# controller.net
KiCad netlist of a schematic drawn in Altium Designer
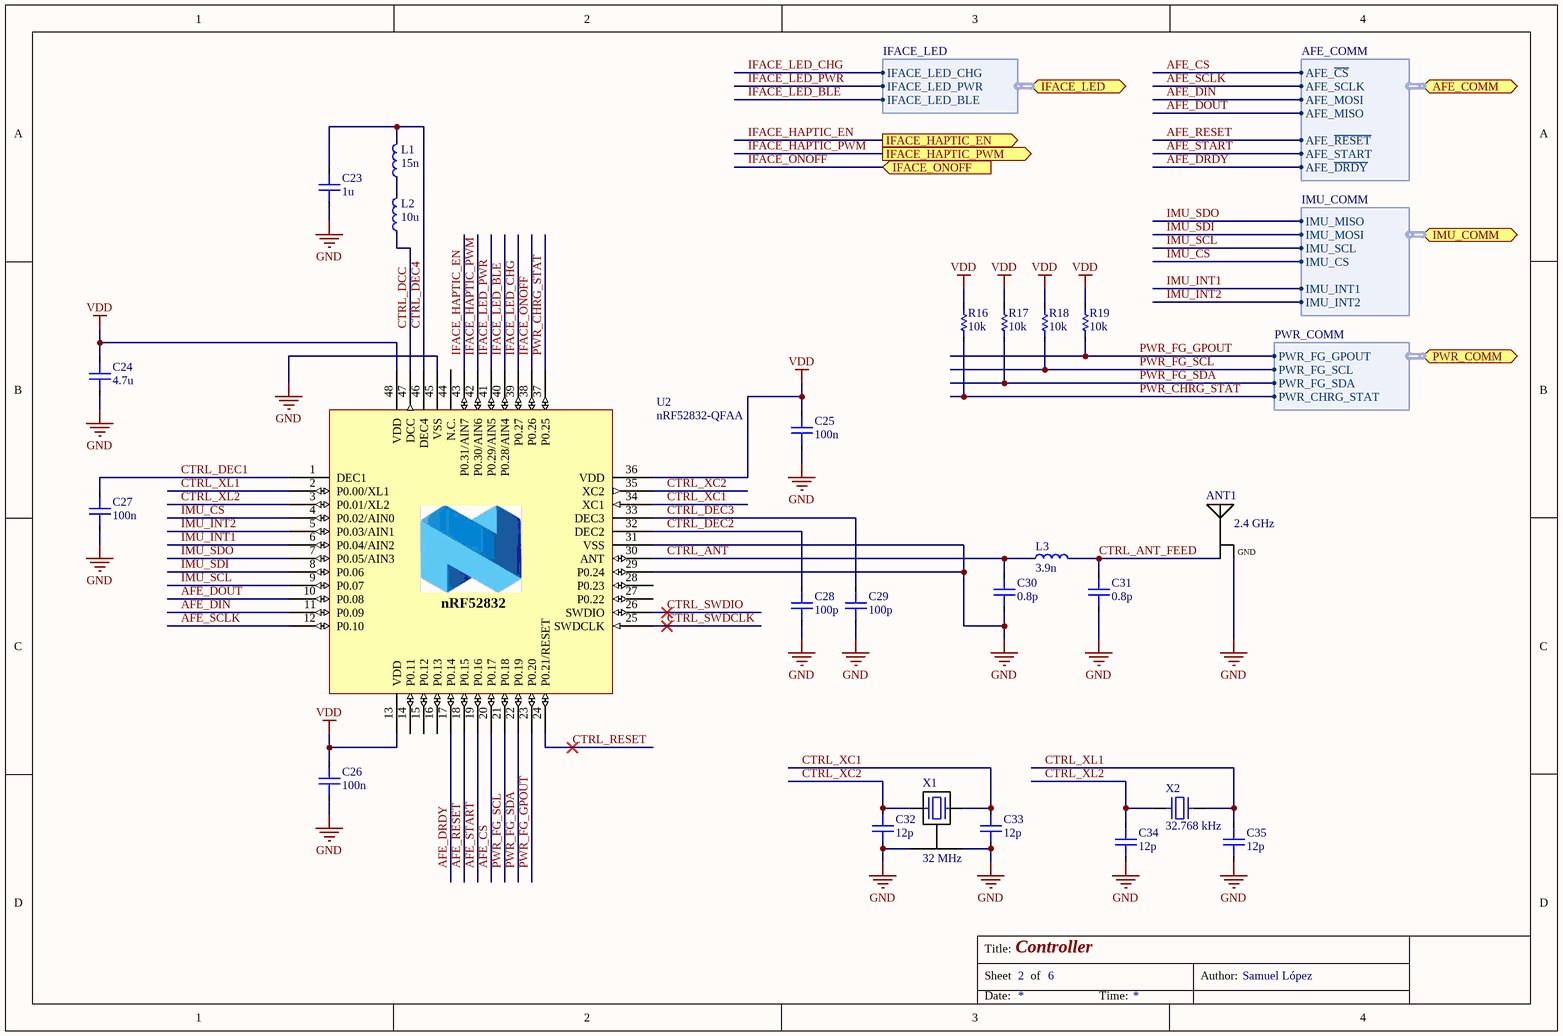
[diagram p0: controller.SchDoc]

(export (version "E")
  (design (tool "Eeschema 10.0.6"))
  (components
    (comp (ref "ANT1")
      (value "2.4 GHz")
      (footprint "ANT2.4GHZ_MIFA")
      (description "Antenna - Meandered Inverted F Antenna (IFA)")
      (libsource (lib "ecg-go") (part "Antenna 2.4 GHz"))
    )
    (comp (ref "C23")
      (value "1u")
      (footprint "C0402")
      (description "Capacitor")
      (libsource (lib "misc") (part "Capacitor"))
    )
    (comp (ref "C24")
      (value "4.7u")
      (footprint "C0603")
      (description "Capacitor")
      (libsource (lib "misc") (part "Capacitor"))
    )
    (comp (ref "C25")
      (value "100n")
      (footprint "C0402")
      (description "Capacitor")
      (libsource (lib "misc") (part "Capacitor"))
    )
    (comp (ref "C26")
      (value "100n")
      (footprint "C0402")
      (description "Capacitor")
      (libsource (lib "misc") (part "Capacitor"))
    )
    (comp (ref "C27")
      (value "100n")
      (footprint "C0402")
      (description "Capacitor")
      (libsource (lib "misc") (part "Capacitor"))
    )
    (comp (ref "C28")
      (value "100p")
      (footprint "C0402")
      (description "Capacitor")
      (libsource (lib "misc") (part "Capacitor"))
    )
    (comp (ref "C29")
      (value "100p")
      (footprint "C0402")
      (description "Capacitor")
      (libsource (lib "misc") (part "Capacitor"))
    )
    (comp (ref "C30")
      (value "0.8p")
      (footprint "C0402")
      (description "Capacitor")
      (libsource (lib "misc") (part "Capacitor"))
    )
    (comp (ref "C31")
      (value "0.8p")
      (footprint "C0402")
      (description "Capacitor")
      (libsource (lib "misc") (part "Capacitor"))
    )
    (comp (ref "C32")
      (value "12p")
      (footprint "C0402")
      (description "Capacitor")
      (libsource (lib "misc") (part "Capacitor"))
    )
    (comp (ref "C33")
      (value "12p")
      (footprint "C0402")
      (description "Capacitor")
      (libsource (lib "misc") (part "Capacitor"))
    )
    (comp (ref "C34")
      (value "12p")
      (footprint "C0402")
      (description "Capacitor")
      (libsource (lib "misc") (part "Capacitor"))
    )
    (comp (ref "C35")
      (value "12p")
      (footprint "C0402")
      (description "Capacitor")
      (libsource (lib "misc") (part "Capacitor"))
    )
    (comp (ref "L1")
      (value "15n")
      (footprint "L0402")
      (description "Inductor")
      (libsource (lib "misc") (part "Inductor"))
    )
    (comp (ref "L2")
      (value "10u")
      (footprint "L0603")
      (description "Inductor")
      (libsource (lib "misc") (part "Inductor"))
    )
    (comp (ref "L3")
      (value "3.9n")
      (footprint "L0402")
      (description "Inductor")
      (libsource (lib "misc") (part "Inductor"))
    )
    (comp (ref "R16")
      (value "10k")
      (footprint "R0402")
      (description "Resistor")
      (libsource (lib "misc") (part "Resistor"))
    )
    (comp (ref "R17")
      (value "10k")
      (footprint "R0402")
      (description "Resistor")
      (libsource (lib "misc") (part "Resistor"))
    )
    (comp (ref "R18")
      (value "10k")
      (footprint "R0402")
      (description "Resistor")
      (libsource (lib "misc") (part "Resistor"))
    )
    (comp (ref "R19")
      (value "10k")
      (footprint "R0402")
      (description "Resistor")
      (libsource (lib "misc") (part "Resistor"))
    )
    (comp (ref "U2")
      (value "nRF52832-QFAA")
      (footprint "QFN40P600X600X90-48N")
      (description "Multi-protocol Bluetooth Low Energy, ANT and 2.4GHz proprietary system-on-chip")
      (fields
        (field (name "MANUFACTURER") "Nordic Semiconductor")
        (field (name "PUBLISHER") "Nordic Semiconductor")
      )
      (libsource (lib "nrf52832_qfax") (part "nRF52832_QFAA"))
    )
    (comp (ref "X1")
      (value "32 MHz")
      (footprint "CX2016DB32000D0FLJCC")
      (description "Crystal - 32 MHz, 8 pF, 80 ohm")
      (libsource (lib "ecg-go") (part "CX2016DB32000D0FLJCC"))
    )
    (comp (ref "X2")
      (value "32.768 kHz")
      (footprint "ABS07-32.768KHZ-9-T")
      (description "Crystal - 32.768 kHz, 9 pF, 70 kOhm")
      (libsource (lib "ecg-go") (part "ABS07-32.768KHZ-9-T"))
    )
  )
  (nets
    (net (code "5") (name "/AFE_CS") (class "Default")
      (node (ref "U2") (pin "20") (pinfunction "P0.17_20") (pintype "bidirectional"))
    )
    (net (code "6") (name "/AFE_DIN") (class "Default")
      (node (ref "U2") (pin "11") (pinfunction "P0.09_11") (pintype "bidirectional"))
    )
    (net (code "7") (name "/AFE_DOUT") (class "Default")
      (node (ref "U2") (pin "10") (pinfunction "P0.08_10") (pintype "bidirectional"))
    )
    (net (code "8") (name "/AFE_DRDY") (class "Default")
      (node (ref "U2") (pin "17") (pinfunction "P0.14_17") (pintype "bidirectional"))
    )
    (net (code "9") (name "/AFE_RESET") (class "Default")
      (node (ref "U2") (pin "18") (pinfunction "P0.15_18") (pintype "bidirectional"))
    )
    (net (code "10") (name "/AFE_SCLK") (class "Default")
      (node (ref "U2") (pin "12") (pinfunction "P0.10_12") (pintype "bidirectional"))
    )
    (net (code "11") (name "/AFE_START") (class "Default")
      (node (ref "U2") (pin "19") (pinfunction "P0.16_19") (pintype "bidirectional"))
    )
    (net (code "12") (name "/CTRL_ANT") (class "Default")
      (node (ref "C30") (pin "1") (pinfunction "1_1") (pintype "passive"))
      (node (ref "L3") (pin "1") (pinfunction "1_1") (pintype "passive"))
      (node (ref "U2") (pin "30") (pinfunction "ANT_30") (pintype "bidirectional"))
    )
    (net (code "13") (name "/CTRL_ANT_FEED") (class "Default")
      (node (ref "ANT1") (pin "1") (pinfunction "IN_1") (pintype "passive"))
      (node (ref "C31") (pin "1") (pinfunction "1_1") (pintype "passive"))
      (node (ref "L3") (pin "2") (pinfunction "2_2") (pintype "passive"))
    )
    (net (code "14") (name "/CTRL_DCC") (class "Default")
      (node (ref "L2") (pin "1") (pinfunction "1_1") (pintype "passive"))
      (node (ref "U2") (pin "47") (pinfunction "DCC_47") (pintype "output"))
    )
    (net (code "15") (name "/CTRL_DEC1") (class "Default")
      (node (ref "C27") (pin "2") (pinfunction "2_2") (pintype "passive"))
      (node (ref "U2") (pin "1") (pinfunction "DEC1_1") (pintype "power_in"))
    )
    (net (code "16") (name "/CTRL_DEC2") (class "Default")
      (node (ref "C28") (pin "2") (pinfunction "2_2") (pintype "passive"))
      (node (ref "U2") (pin "32") (pinfunction "DEC2_32") (pintype "power_in"))
    )
    (net (code "17") (name "/CTRL_DEC3") (class "Default")
      (node (ref "C29") (pin "2") (pinfunction "2_2") (pintype "passive"))
      (node (ref "U2") (pin "33") (pinfunction "DEC3_33") (pintype "power_in"))
    )
    (net (code "18") (name "/CTRL_DEC4") (class "Default")
      (node (ref "C23") (pin "2") (pinfunction "2_2") (pintype "passive"))
      (node (ref "L1") (pin "2") (pinfunction "2_2") (pintype "passive"))
      (node (ref "U2") (pin "46") (pinfunction "DEC4_46") (pintype "power_in"))
    )
    (net (code "22") (name "/CTRL_RESET") (class "Default")
      (node (ref "U2") (pin "24") (pinfunction "P0.21/RESET_24") (pintype "bidirectional"))
    )
    (net (code "23") (name "/CTRL_SWDCLK") (class "Default")
      (node (ref "U2") (pin "25") (pinfunction "SWDCLK_25") (pintype "input"))
    )
    (net (code "24") (name "/CTRL_SWDIO") (class "Default")
      (node (ref "U2") (pin "26") (pinfunction "SWDIO_26") (pintype "bidirectional"))
    )
    (net (code "25") (name "/CTRL_XC1") (class "Default")
      (node (ref "C33") (pin "2") (pinfunction "2_2") (pintype "passive"))
      (node (ref "U2") (pin "34") (pinfunction "XC1_34") (pintype "input"))
      (node (ref "X1") (pin "3") (pinfunction "3_3") (pintype "passive"))
    )
    (net (code "26") (name "/CTRL_XC2") (class "Default")
      (node (ref "C32") (pin "2") (pinfunction "2_2") (pintype "passive"))
      (node (ref "U2") (pin "35") (pinfunction "XC2_35") (pintype "output"))
      (node (ref "X1") (pin "1") (pinfunction "1_1") (pintype "passive"))
    )
    (net (code "27") (name "/CTRL_XL1") (class "Default")
      (node (ref "C35") (pin "2") (pinfunction "2_2") (pintype "passive"))
      (node (ref "U2") (pin "2") (pinfunction "P0.00/XL1_2") (pintype "bidirectional"))
      (node (ref "X2") (pin "2") (pinfunction "2_2") (pintype "passive"))
    )
    (net (code "28") (name "/CTRL_XL2") (class "Default")
      (node (ref "C34") (pin "2") (pinfunction "2_2") (pintype "passive"))
      (node (ref "U2") (pin "3") (pinfunction "P0.01/XL2_3") (pintype "bidirectional"))
      (node (ref "X2") (pin "1") (pinfunction "1_1") (pintype "passive"))
    )
    (net (code "29") (name "/IFACE_HAPTIC_EN") (class "Default")
      (node (ref "U2") (pin "43") (pinfunction "P0.31/AIN7_43") (pintype "bidirectional"))
    )
    (net (code "30") (name "/IFACE_HAPTIC_PWM") (class "Default")
      (node (ref "U2") (pin "42") (pinfunction "P0.30/AIN6_42") (pintype "bidirectional"))
    )
    (net (code "31") (name "/IFACE_LED_BLE") (class "Default")
      (node (ref "U2") (pin "40") (pinfunction "P0.28/AIN4_40") (pintype "bidirectional"))
    )
    (net (code "32") (name "/IFACE_LED_CHG") (class "Default")
      (node (ref "U2") (pin "39") (pinfunction "P0.27_39") (pintype "bidirectional"))
    )
    (net (code "33") (name "/IFACE_LED_PWR") (class "Default")
      (node (ref "U2") (pin "41") (pinfunction "P0.29/AIN5_41") (pintype "bidirectional"))
    )
    (net (code "34") (name "/IFACE_ONOFF") (class "Default")
      (node (ref "U2") (pin "38") (pinfunction "P0.26_38") (pintype "bidirectional"))
    )
    (net (code "35") (name "/IMU_CS") (class "Default")
      (node (ref "U2") (pin "4") (pinfunction "P0.02/AIN0_4") (pintype "bidirectional"))
    )
    (net (code "36") (name "/IMU_INT1") (class "Default")
      (node (ref "U2") (pin "6") (pinfunction "P0.04/AIN2_6") (pintype "bidirectional"))
    )
    (net (code "37") (name "/IMU_INT2") (class "Default")
      (node (ref "U2") (pin "5") (pinfunction "P0.03/AIN1_5") (pintype "bidirectional"))
    )
    (net (code "38") (name "/IMU_SCL") (class "Default")
      (node (ref "U2") (pin "9") (pinfunction "P0.07_9") (pintype "bidirectional"))
    )
    (net (code "39") (name "/IMU_SDI") (class "Default")
      (node (ref "U2") (pin "8") (pinfunction "P0.06_8") (pintype "bidirectional"))
    )
    (net (code "40") (name "/IMU_SDO") (class "Default")
      (node (ref "U2") (pin "7") (pinfunction "P0.05/AIN3_7") (pintype "bidirectional"))
    )
    (net (code "41") (name "/PWR_CHRG_STAT") (class "Default")
      (node (ref "R16") (pin "1") (pinfunction "1_1") (pintype "passive"))
      (node (ref "U2") (pin "37") (pinfunction "P0.25_37") (pintype "bidirectional"))
    )
    (net (code "46") (name "/PWR_FG_GPOUT") (class "Default")
      (node (ref "R19") (pin "1") (pinfunction "1_1") (pintype "passive"))
      (node (ref "U2") (pin "23") (pinfunction "P0.20_23") (pintype "bidirectional"))
    )
    (net (code "47") (name "/PWR_FG_SCL") (class "Default")
      (node (ref "R18") (pin "1") (pinfunction "1_1") (pintype "passive"))
      (node (ref "U2") (pin "21") (pinfunction "P0.18_21") (pintype "bidirectional"))
    )
    (net (code "48") (name "/PWR_FG_SDA") (class "Default")
      (node (ref "R17") (pin "1") (pinfunction "1_1") (pintype "passive"))
      (node (ref "U2") (pin "22") (pinfunction "P0.19_22") (pintype "bidirectional"))
    )
    (net (code "49") (name "GND") (class "Default")
      (node (ref "ANT1") (pin "2") (pinfunction "GND_2") (pintype "passive"))
      (node (ref "C23") (pin "1") (pinfunction "1_1") (pintype "passive"))
      (node (ref "C24") (pin "1") (pinfunction "1_1") (pintype "passive"))
      (node (ref "C25") (pin "1") (pinfunction "1_1") (pintype "passive"))
      (node (ref "C26") (pin "1") (pinfunction "1_1") (pintype "passive"))
      (node (ref "C27") (pin "1") (pinfunction "1_1") (pintype "passive"))
      (node (ref "C28") (pin "1") (pinfunction "1_1") (pintype "passive"))
      (node (ref "C29") (pin "1") (pinfunction "1_1") (pintype "passive"))
      (node (ref "C30") (pin "2") (pinfunction "2_2") (pintype "passive"))
      (node (ref "C31") (pin "2") (pinfunction "2_2") (pintype "passive"))
      (node (ref "C32") (pin "1") (pinfunction "1_1") (pintype "passive"))
      (node (ref "C33") (pin "1") (pinfunction "1_1") (pintype "passive"))
      (node (ref "C34") (pin "1") (pinfunction "1_1") (pintype "passive"))
      (node (ref "C35") (pin "1") (pinfunction "1_1") (pintype "passive"))
      (node (ref "U2") (pin "29") (pinfunction "P0.24_29") (pintype "bidirectional"))
      (node (ref "U2") (pin "31") (pinfunction "VSS_31") (pintype "power_in"))
      (node (ref "U2") (pin "45") (pinfunction "VSS_45") (pintype "power_in"))
      (node (ref "U2") (pin "49") (pinfunction "GND_49") (pintype "power_in"))
      (node (ref "X1") (pin "2") (pinfunction "2_2") (pintype "passive"))
      (node (ref "X1") (pin "4") (pinfunction "4_4") (pintype "passive"))
    )
    (net (code "50") (name "Net-(L1-Pad1)") (class "Default")
      (node (ref "L1") (pin "1") (pinfunction "1_1") (pintype "passive"))
      (node (ref "L2") (pin "2") (pinfunction "2_2") (pintype "passive"))
    )
    (net (code "51") (name "VDD") (class "Default")
      (node (ref "C24") (pin "2") (pinfunction "2_2") (pintype "passive"))
      (node (ref "C25") (pin "2") (pinfunction "2_2") (pintype "passive"))
      (node (ref "C26") (pin "2") (pinfunction "2_2") (pintype "passive"))
      (node (ref "R16") (pin "2") (pinfunction "2_2") (pintype "passive"))
      (node (ref "R17") (pin "2") (pinfunction "2_2") (pintype "passive"))
      (node (ref "R18") (pin "2") (pinfunction "2_2") (pintype "passive"))
      (node (ref "R19") (pin "2") (pinfunction "2_2") (pintype "passive"))
      (node (ref "U2") (pin "13") (pinfunction "VDD_13") (pintype "power_in"))
      (node (ref "U2") (pin "36") (pinfunction "VDD_36") (pintype "power_in"))
      (node (ref "U2") (pin "48") (pinfunction "VDD_48") (pintype "power_in"))
    )
    (net (code "52") (name "unconnected-(U2-N.C.-Pad44)") (class "Default")
      (node (ref "U2") (pin "44") (pinfunction "N.C._44") (pintype "power_in"))
    )
    (net (code "53") (name "unconnected-(U2-P0.11-Pad14)") (class "Default")
      (node (ref "U2") (pin "14") (pinfunction "P0.11_14") (pintype "bidirectional"))
    )
    (net (code "54") (name "unconnected-(U2-P0.12-Pad15)") (class "Default")
      (node (ref "U2") (pin "15") (pinfunction "P0.12_15") (pintype "bidirectional"))
    )
    (net (code "55") (name "unconnected-(U2-P0.13-Pad16)") (class "Default")
      (node (ref "U2") (pin "16") (pinfunction "P0.13_16") (pintype "bidirectional"))
    )
    (net (code "56") (name "unconnected-(U2-P0.22-Pad27)") (class "Default")
      (node (ref "U2") (pin "27") (pinfunction "P0.22_27") (pintype "bidirectional"))
    )
    (net (code "57") (name "unconnected-(U2-P0.23-Pad28)") (class "Default")
      (node (ref "U2") (pin "28") (pinfunction "P0.23_28") (pintype "bidirectional"))
    )
  )
)
